# MA-USBC.net
KiCad netlist of a schematic drawn in Altium Designer
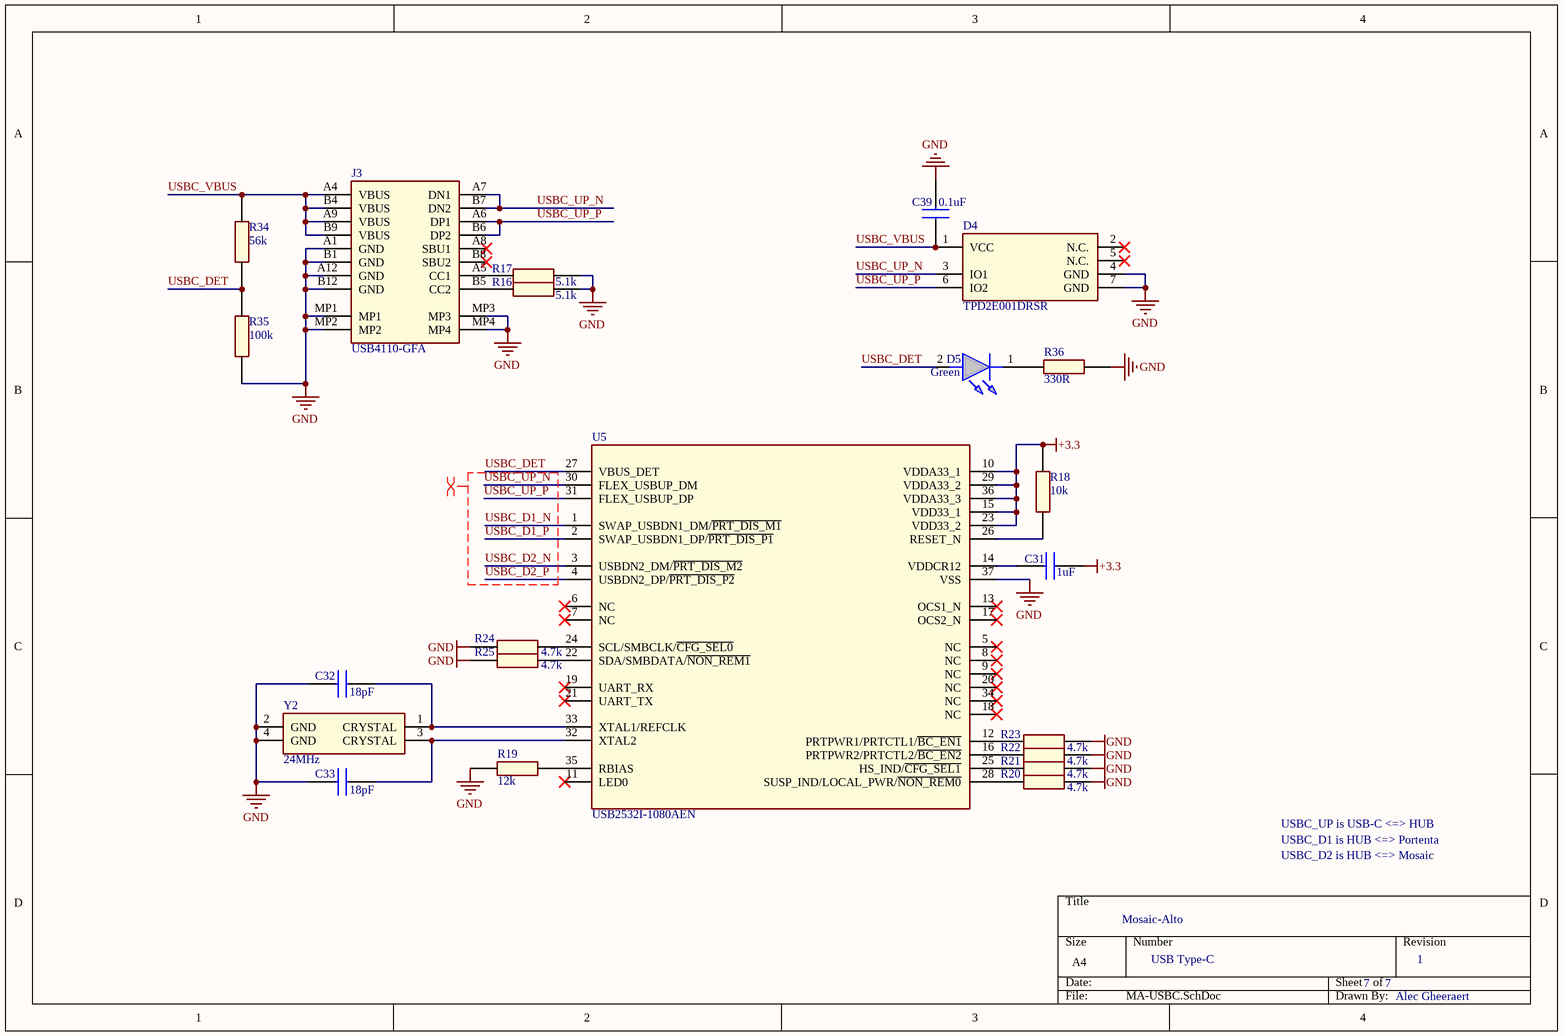
[diagram p0: MA-USBC.SchDoc]

(export (version "E")
  (design (tool "Eeschema 10.0.6"))
  (components
    (comp (ref "C31")
      (value "1uF")
      (footprint "CAPC1608X100N")
      (description "0603 1µF")
      (fields (field (name "MANUFACTURER") "Walsin") (field (name "TOLERANCE") "10%"))
      (libsource (lib "Ghrt") (part "0603X105K6R3CT"))
    )
    (comp (ref "C32")
      (value "18pF")
      (footprint "CAPC1608X87N")
      (description "0603 18pF")
      (fields (field (name "TOLERANCE") "5%") (field (name "MANUFACTURER") "Walsin"))
      (libsource (lib "Ghrt") (part "0603N180J160CT"))
    )
    (comp (ref "C33")
      (value "18pF")
      (footprint "CAPC1608X87N")
      (description "0603 18pF")
      (fields (field (name "TOLERANCE") "5%") (field (name "MANUFACTURER") "Walsin"))
      (libsource (lib "Ghrt") (part "0603N180J160CT"))
    )
    (comp (ref "C39")
      (value "0.1uF")
      (footprint "CAPC2012X145N")
      (description "0805I 0.1µF")
      (fields (field (name "MANUFACTURER") "Walsin") (field (name "TOLERANCE") "10%"))
      (libsource (lib "Ghrt") (part "MG21B104K101CT"))
    )
    (comp (ref "D4")
      (value "TPD2E001DRSR")
      (footprint "SON95P300X300X80-7N-D")
      (description "2-Channel TVS Diode")
      (libsource (lib "Ghrt") (part "TPD2E001DRSR"))
    )
    (comp (ref "D5")
      (value "Green")
      (footprint "APT1608ZGCAMT")
      (description "0603 Green LED")
      (libsource (lib "Ghrt") (part "APT1608ZGC-AMT"))
    )
    (comp (ref "J3")
      (value "USB4110-GFA")
      (footprint "USB4110-GFA")
      (description "USB-2.0 Type C")
      (fields (field (name "MANUFACTURER") "Global Connector Technologies"))
      (libsource (lib "Ghrt") (part "USB4110-GFA"))
    )
    (comp (ref "R16")
      (value "5.1k")
      (footprint "RESC1608X60N")
      (description "0603I 5.1k")
      (fields (field (name "MANUFACTURER") "Walsin") (field (name "TOLERANCE") "1%"))
      (libsource (lib "Ghrt") (part "WR06X5101FTL"))
    )
    (comp (ref "R17")
      (value "5.1k")
      (footprint "RESC1608X60N")
      (description "0603I 5.1k")
      (fields (field (name "MANUFACTURER") "Walsin") (field (name "TOLERANCE") "1%"))
      (libsource (lib "Ghrt") (part "WR06X5101FTL"))
    )
    (comp (ref "R18")
      (value "10k")
      (footprint "RESC1005X40N")
      (description "0402I 10k")
      (fields (field (name "MANUFACTURER") "Walsin") (field (name "TOLERANCE") "1%"))
      (libsource (lib "Ghrt") (part "WR04X1002FTL"))
    )
    (comp (ref "R19")
      (value "12k")
      (footprint "RESC1005X40N")
      (description "0402I 12k")
      (fields (field (name "TOLERANCE") "1%") (field (name "MANUFACTURER") "Walsin"))
      (libsource (lib "Ghrt") (part "WR04X1202FTL"))
    )
    (comp (ref "R20")
      (value "4.7k")
      (footprint "RESC1005X40N")
      (description "0402I 4.7k")
      (fields (field (name "MANUFACTURER") "Walsin") (field (name "TOLERANCE") "1%"))
      (libsource (lib "Ghrt") (part "WR04X4701FTL"))
    )
    (comp (ref "R21")
      (value "4.7k")
      (footprint "RESC1005X40N")
      (description "0402I 4.7k")
      (fields (field (name "MANUFACTURER") "Walsin") (field (name "TOLERANCE") "1%"))
      (libsource (lib "Ghrt") (part "WR04X4701FTL"))
    )
    (comp (ref "R22")
      (value "4.7k")
      (footprint "RESC1005X40N")
      (description "0402I 4.7k")
      (fields (field (name "MANUFACTURER") "Walsin") (field (name "TOLERANCE") "1%"))
      (libsource (lib "Ghrt") (part "WR04X4701FTL"))
    )
    (comp (ref "R23")
      (value "4.7k")
      (footprint "RESC1005X40N")
      (description "0402I 4.7k")
      (fields (field (name "MANUFACTURER") "Walsin") (field (name "TOLERANCE") "1%"))
      (libsource (lib "Ghrt") (part "WR04X4701FTL"))
    )
    (comp (ref "R24")
      (value "4.7k")
      (footprint "RESC1005X40N")
      (description "0402I 4.7k")
      (fields (field (name "MANUFACTURER") "Walsin") (field (name "TOLERANCE") "1%"))
      (libsource (lib "Ghrt") (part "WR04X4701FTL"))
    )
    (comp (ref "R25")
      (value "4.7k")
      (footprint "RESC1005X40N")
      (description "0402I 4.7k")
      (fields (field (name "MANUFACTURER") "Walsin") (field (name "TOLERANCE") "1%"))
      (libsource (lib "Ghrt") (part "WR04X4701FTL"))
    )
    (comp (ref "R34")
      (value "56k")
      (footprint "RESC1005X40N")
      (description "0402I 56k")
      (fields (field (name "TOLERANCE") "1%") (field (name "MANUFACTURER") "Walsin"))
      (libsource (lib "Ghrt") (part "WR04X5602FTL"))
    )
    (comp (ref "R35")
      (value "100k")
      (footprint "RESC1005X40N")
      (description "0402I 100k")
      (fields (field (name "MANUFACTURER") "Walsin") (field (name "TOLERANCE") "1%"))
      (libsource (lib "Ghrt") (part "WR04X1003FTL"))
    )
    (comp (ref "R36")
      (value "330R")
      (footprint "RESC1005X40N")
      (description "0402I 330")
      (fields (field (name "TOLERANCE") "1%") (field (name "MANUFACTURER") "Walsin"))
      (libsource (lib "Ghrt") (part "WR04X3300FTL"))
    )
    (comp (ref "U5")
      (value "USB2532I-1080AEN")
      (footprint "QFN50P600X600X100-37N-D")
      (description "2-Port USB-2.0 Controller Hub")
      (fields (field (name "MANUFACTURER") "Microchip"))
      (libsource (lib "Ghrt") (part "USB2532I-1080AEN"))
    )
    (comp (ref "Y2")
      (value "24MHz")
      (footprint "LFXTAL071257Reel")
      (description "24MHz +/-100ppm Crystal")
      (fields (field (name "TOLERANCE") "10") (field (name "MANUFACTURER") "IQD"))
      (libsource (lib "Ghrt") (part "LFXTAL071257Reel"))
    )
  )
  (nets
    (net (code "1") (name "+3.3") (class "Default")
      (node (ref "C31") (pin "2") (pinfunction "2_2") (pintype "passive"))
      (node (ref "R18") (pin "2") (pinfunction "2_2") (pintype "passive"))
      (node (ref "U5") (pin "10") (pinfunction "VDDA33_1_10") (pintype "passive"))
      (node (ref "U5") (pin "15") (pinfunction "VDD33_1_15") (pintype "passive"))
      (node (ref "U5") (pin "23") (pinfunction "VDD33_2_23") (pintype "passive"))
      (node (ref "U5") (pin "29") (pinfunction "VDDA33_2_29") (pintype "passive"))
      (node (ref "U5") (pin "36") (pinfunction "VDDA33_3_36") (pintype "passive"))
    )
    (net (code "3") (name "/USBC_D1_N") (class "Default")
      (node (ref "U5") (pin "1") (pinfunction "SWAP_USBDN1_DM/~{PRT_DIS_M1}_1") (pintype "passive"))
    )
    (net (code "4") (name "/USBC_D1_P") (class "Default")
      (node (ref "U5") (pin "2") (pinfunction "SWAP_USBDN1_DP/~{PRT_DIS_P1}_2") (pintype "passive"))
    )
    (net (code "5") (name "/USBC_D2_N") (class "Default")
      (node (ref "U5") (pin "3") (pinfunction "USBDN2_DM/~{PRT_DIS_M2}_3") (pintype "passive"))
    )
    (net (code "6") (name "/USBC_D2_P") (class "Default")
      (node (ref "U5") (pin "4") (pinfunction "USBDN2_DP/~{PRT_DIS_P2}_4") (pintype "passive"))
    )
    (net (code "7") (name "/USBC_DET") (class "Default")
      (node (ref "D5") (pin "2") (pinfunction "A_2") (pintype "passive"))
      (node (ref "R34") (pin "2") (pinfunction "2_2") (pintype "passive"))
      (node (ref "R35") (pin "1") (pinfunction "1_1") (pintype "passive"))
      (node (ref "U5") (pin "27") (pinfunction "VBUS_DET_27") (pintype "passive"))
    )
    (net (code "8") (name "/USBC_UP_N") (class "Default")
      (node (ref "D4") (pin "3") (pinfunction "IO1_3") (pintype "passive"))
      (node (ref "J3") (pin "A7") (pinfunction "DN1_A7") (pintype "passive"))
      (node (ref "J3") (pin "B7") (pinfunction "DN2_B7") (pintype "passive"))
      (node (ref "U5") (pin "30") (pinfunction "FLEX_USBUP_DM_30") (pintype "passive"))
    )
    (net (code "9") (name "/USBC_UP_P") (class "Default")
      (node (ref "D4") (pin "6") (pinfunction "IO2_6") (pintype "passive"))
      (node (ref "J3") (pin "A6") (pinfunction "DP1_A6") (pintype "passive"))
      (node (ref "J3") (pin "B6") (pinfunction "DP2_B6") (pintype "passive"))
      (node (ref "U5") (pin "31") (pinfunction "FLEX_USBUP_DP_31") (pintype "passive"))
    )
    (net (code "10") (name "/USBC_VBUS") (class "Default")
      (node (ref "C39") (pin "1") (pinfunction "1_1") (pintype "passive"))
      (node (ref "D4") (pin "1") (pinfunction "VCC_1") (pintype "passive"))
      (node (ref "J3") (pin "A4") (pinfunction "VBUS_A4") (pintype "passive"))
      (node (ref "J3") (pin "A9") (pinfunction "VBUS_A9") (pintype "passive"))
      (node (ref "J3") (pin "B4") (pinfunction "VBUS_B4") (pintype "passive"))
      (node (ref "J3") (pin "B9") (pinfunction "VBUS_B9") (pintype "passive"))
      (node (ref "R34") (pin "1") (pinfunction "1_1") (pintype "passive"))
    )
    (net (code "11") (name "GND") (class "Default")
      (node (ref "C32") (pin "1") (pinfunction "1_1") (pintype "passive"))
      (node (ref "C33") (pin "1") (pinfunction "1_1") (pintype "passive"))
      (node (ref "C39") (pin "2") (pinfunction "2_2") (pintype "passive"))
      (node (ref "D4") (pin "4") (pinfunction "GND_4") (pintype "passive"))
      (node (ref "D4") (pin "7") (pinfunction "GND_7") (pintype "passive"))
      (node (ref "J3") (pin "A1") (pinfunction "GND_A1") (pintype "passive"))
      (node (ref "J3") (pin "A12") (pinfunction "GND_A12") (pintype "passive"))
      (node (ref "J3") (pin "B1") (pinfunction "GND_B1") (pintype "passive"))
      (node (ref "J3") (pin "B12") (pinfunction "GND_B12") (pintype "passive"))
      (node (ref "J3") (pin "MP1") (pinfunction "MP1_MP1") (pintype "passive"))
      (node (ref "J3") (pin "MP2") (pinfunction "MP2_MP2") (pintype "passive"))
      (node (ref "J3") (pin "MP3") (pinfunction "MP3_MP3") (pintype "passive"))
      (node (ref "J3") (pin "MP4") (pinfunction "MP4_MP4") (pintype "passive"))
      (node (ref "R16") (pin "2") (pinfunction "2_2") (pintype "passive"))
      (node (ref "R17") (pin "2") (pinfunction "2_2") (pintype "passive"))
      (node (ref "R19") (pin "2") (pinfunction "2_2") (pintype "passive"))
      (node (ref "R20") (pin "2") (pinfunction "2_2") (pintype "passive"))
      (node (ref "R21") (pin "2") (pinfunction "2_2") (pintype "passive"))
      (node (ref "R22") (pin "2") (pinfunction "2_2") (pintype "passive"))
      (node (ref "R23") (pin "2") (pinfunction "2_2") (pintype "passive"))
      (node (ref "R24") (pin "1") (pinfunction "1_1") (pintype "passive"))
      (node (ref "R25") (pin "1") (pinfunction "1_1") (pintype "passive"))
      (node (ref "R35") (pin "2") (pinfunction "2_2") (pintype "passive"))
      (node (ref "R36") (pin "2") (pinfunction "2_2") (pintype "passive"))
      (node (ref "U5") (pin "37") (pinfunction "VSS_37") (pintype "passive"))
      (node (ref "Y2") (pin "2") (pinfunction "GND_2") (pintype "passive"))
      (node (ref "Y2") (pin "4") (pinfunction "GND_4") (pintype "passive"))
    )
    (net (code "12") (name "Net-(D5-K)") (class "Default")
      (node (ref "D5") (pin "1") (pinfunction "K_1") (pintype "passive"))
      (node (ref "R36") (pin "1") (pinfunction "1_1") (pintype "passive"))
    )
    (net (code "13") (name "Net-(J3-CC1)") (class "Default")
      (node (ref "J3") (pin "A5") (pinfunction "CC1_A5") (pintype "passive"))
      (node (ref "R17") (pin "1") (pinfunction "1_1") (pintype "passive"))
    )
    (net (code "14") (name "Net-(J3-CC2)") (class "Default")
      (node (ref "J3") (pin "B5") (pinfunction "CC2_B5") (pintype "passive"))
      (node (ref "R16") (pin "1") (pinfunction "1_1") (pintype "passive"))
    )
    (net (code "15") (name "Net-(U5-HS_IND{slash}~{CFG_SEL1})") (class "Default")
      (node (ref "R21") (pin "1") (pinfunction "1_1") (pintype "passive"))
      (node (ref "U5") (pin "25") (pinfunction "HS_IND/~{CFG_SEL1}_25") (pintype "passive"))
    )
    (net (code "16") (name "Net-(U5-PRTPWR1{slash}PRTCTL1{slash}~{BC_EN1})") (class "Default")
      (node (ref "R23") (pin "1") (pinfunction "1_1") (pintype "passive"))
      (node (ref "U5") (pin "12") (pinfunction "PRTPWR1/PRTCTL1/~{BC_EN1}_12") (pintype "passive"))
    )
    (net (code "17") (name "Net-(U5-PRTPWR2{slash}PRTCTL2{slash}~{BC_EN2})") (class "Default")
      (node (ref "R22") (pin "1") (pinfunction "1_1") (pintype "passive"))
      (node (ref "U5") (pin "16") (pinfunction "PRTPWR2/PRTCTL2/~{BC_EN2}_16") (pintype "passive"))
    )
    (net (code "18") (name "Net-(U5-RBIAS)") (class "Default")
      (node (ref "R19") (pin "1") (pinfunction "1_1") (pintype "passive"))
      (node (ref "U5") (pin "35") (pinfunction "RBIAS_35") (pintype "passive"))
    )
    (net (code "19") (name "Net-(U5-RESET_N)") (class "Default")
      (node (ref "R18") (pin "1") (pinfunction "1_1") (pintype "passive"))
      (node (ref "U5") (pin "26") (pinfunction "RESET_N_26") (pintype "passive"))
    )
    (net (code "20") (name "Net-(U5-SCL{slash}SMBCLK{slash}~{CFG_SEL0})") (class "Default")
      (node (ref "R24") (pin "2") (pinfunction "2_2") (pintype "passive"))
      (node (ref "U5") (pin "24") (pinfunction "SCL/SMBCLK/~{CFG_SEL0}_24") (pintype "passive"))
    )
    (net (code "21") (name "Net-(U5-SDA{slash}SMBDATA{slash}~{NON_REM1})") (class "Default")
      (node (ref "R25") (pin "2") (pinfunction "2_2") (pintype "passive"))
      (node (ref "U5") (pin "22") (pinfunction "SDA/SMBDATA/~{NON_REM1}_22") (pintype "passive"))
    )
    (net (code "22") (name "Net-(U5-SUSP_IND{slash}LOCAL_PWR{slash}~{NON_REM0})") (class "Default")
      (node (ref "R20") (pin "1") (pinfunction "1_1") (pintype "passive"))
      (node (ref "U5") (pin "28") (pinfunction "SUSP_IND/LOCAL_PWR/~{NON_REM0}_28") (pintype "passive"))
    )
    (net (code "23") (name "Net-(U5-VDDCR12)") (class "Default")
      (node (ref "C31") (pin "1") (pinfunction "1_1") (pintype "passive"))
      (node (ref "U5") (pin "14") (pinfunction "VDDCR12_14") (pintype "passive"))
    )
    (net (code "24") (name "Net-(U5-XTAL1{slash}REFCLK)") (class "Default")
      (node (ref "C32") (pin "2") (pinfunction "2_2") (pintype "passive"))
      (node (ref "U5") (pin "33") (pinfunction "XTAL1/REFCLK_33") (pintype "passive"))
      (node (ref "Y2") (pin "1") (pinfunction "CRYSTAL_1") (pintype "passive"))
    )
    (net (code "25") (name "Net-(U5-XTAL2)") (class "Default")
      (node (ref "C33") (pin "2") (pinfunction "2_2") (pintype "passive"))
      (node (ref "U5") (pin "32") (pinfunction "XTAL2_32") (pintype "passive"))
      (node (ref "Y2") (pin "3") (pinfunction "CRYSTAL_3") (pintype "passive"))
    )
    (net (code "26") (name "unconnected-(D4-N.C.-Pad2)") (class "Default")
      (node (ref "D4") (pin "2") (pinfunction "N.C._2") (pintype "passive+no_connect"))
    )
    (net (code "27") (name "unconnected-(D4-N.C.-Pad5)") (class "Default")
      (node (ref "D4") (pin "5") (pinfunction "N.C._5") (pintype "passive+no_connect"))
    )
    (net (code "28") (name "unconnected-(J3-SBU1-PadA8)") (class "Default")
      (node (ref "J3") (pin "A8") (pinfunction "SBU1_A8") (pintype "passive+no_connect"))
    )
    (net (code "29") (name "unconnected-(J3-SBU2-PadB8)") (class "Default")
      (node (ref "J3") (pin "B8") (pinfunction "SBU2_B8") (pintype "passive+no_connect"))
    )
    (net (code "30") (name "unconnected-(U5-LED0-Pad11)") (class "Default")
      (node (ref "U5") (pin "11") (pinfunction "LED0_11") (pintype "passive+no_connect"))
    )
    (net (code "31") (name "unconnected-(U5-NC-Pad5)") (class "Default")
      (node (ref "U5") (pin "5") (pinfunction "NC_5") (pintype "passive+no_connect"))
    )
    (net (code "32") (name "unconnected-(U5-NC-Pad6)") (class "Default")
      (node (ref "U5") (pin "6") (pinfunction "NC_6") (pintype "passive+no_connect"))
    )
    (net (code "33") (name "unconnected-(U5-NC-Pad7)") (class "Default")
      (node (ref "U5") (pin "7") (pinfunction "NC_7") (pintype "passive+no_connect"))
    )
    (net (code "34") (name "unconnected-(U5-NC-Pad8)") (class "Default")
      (node (ref "U5") (pin "8") (pinfunction "NC_8") (pintype "passive+no_connect"))
    )
    (net (code "35") (name "unconnected-(U5-NC-Pad9)") (class "Default")
      (node (ref "U5") (pin "9") (pinfunction "NC_9") (pintype "passive+no_connect"))
    )
    (net (code "36") (name "unconnected-(U5-NC-Pad18)") (class "Default")
      (node (ref "U5") (pin "18") (pinfunction "NC_18") (pintype "passive+no_connect"))
    )
    (net (code "37") (name "unconnected-(U5-NC-Pad20)") (class "Default")
      (node (ref "U5") (pin "20") (pinfunction "NC_20") (pintype "passive+no_connect"))
    )
    (net (code "38") (name "unconnected-(U5-NC-Pad34)") (class "Default")
      (node (ref "U5") (pin "34") (pinfunction "NC_34") (pintype "passive+no_connect"))
    )
    (net (code "39") (name "unconnected-(U5-OCS1_N-Pad13)") (class "Default")
      (node (ref "U5") (pin "13") (pinfunction "OCS1_N_13") (pintype "passive+no_connect"))
    )
    (net (code "40") (name "unconnected-(U5-OCS2_N-Pad17)") (class "Default")
      (node (ref "U5") (pin "17") (pinfunction "OCS2_N_17") (pintype "passive+no_connect"))
    )
    (net (code "41") (name "unconnected-(U5-UART_RX-Pad19)") (class "Default")
      (node (ref "U5") (pin "19") (pinfunction "UART_RX_19") (pintype "passive+no_connect"))
    )
    (net (code "42") (name "unconnected-(U5-UART_TX-Pad21)") (class "Default")
      (node (ref "U5") (pin "21") (pinfunction "UART_TX_21") (pintype "passive+no_connect"))
    )
  )
)
